# Sparki_Rev15.net
KiCad netlist of a schematic drawn in EAGLE
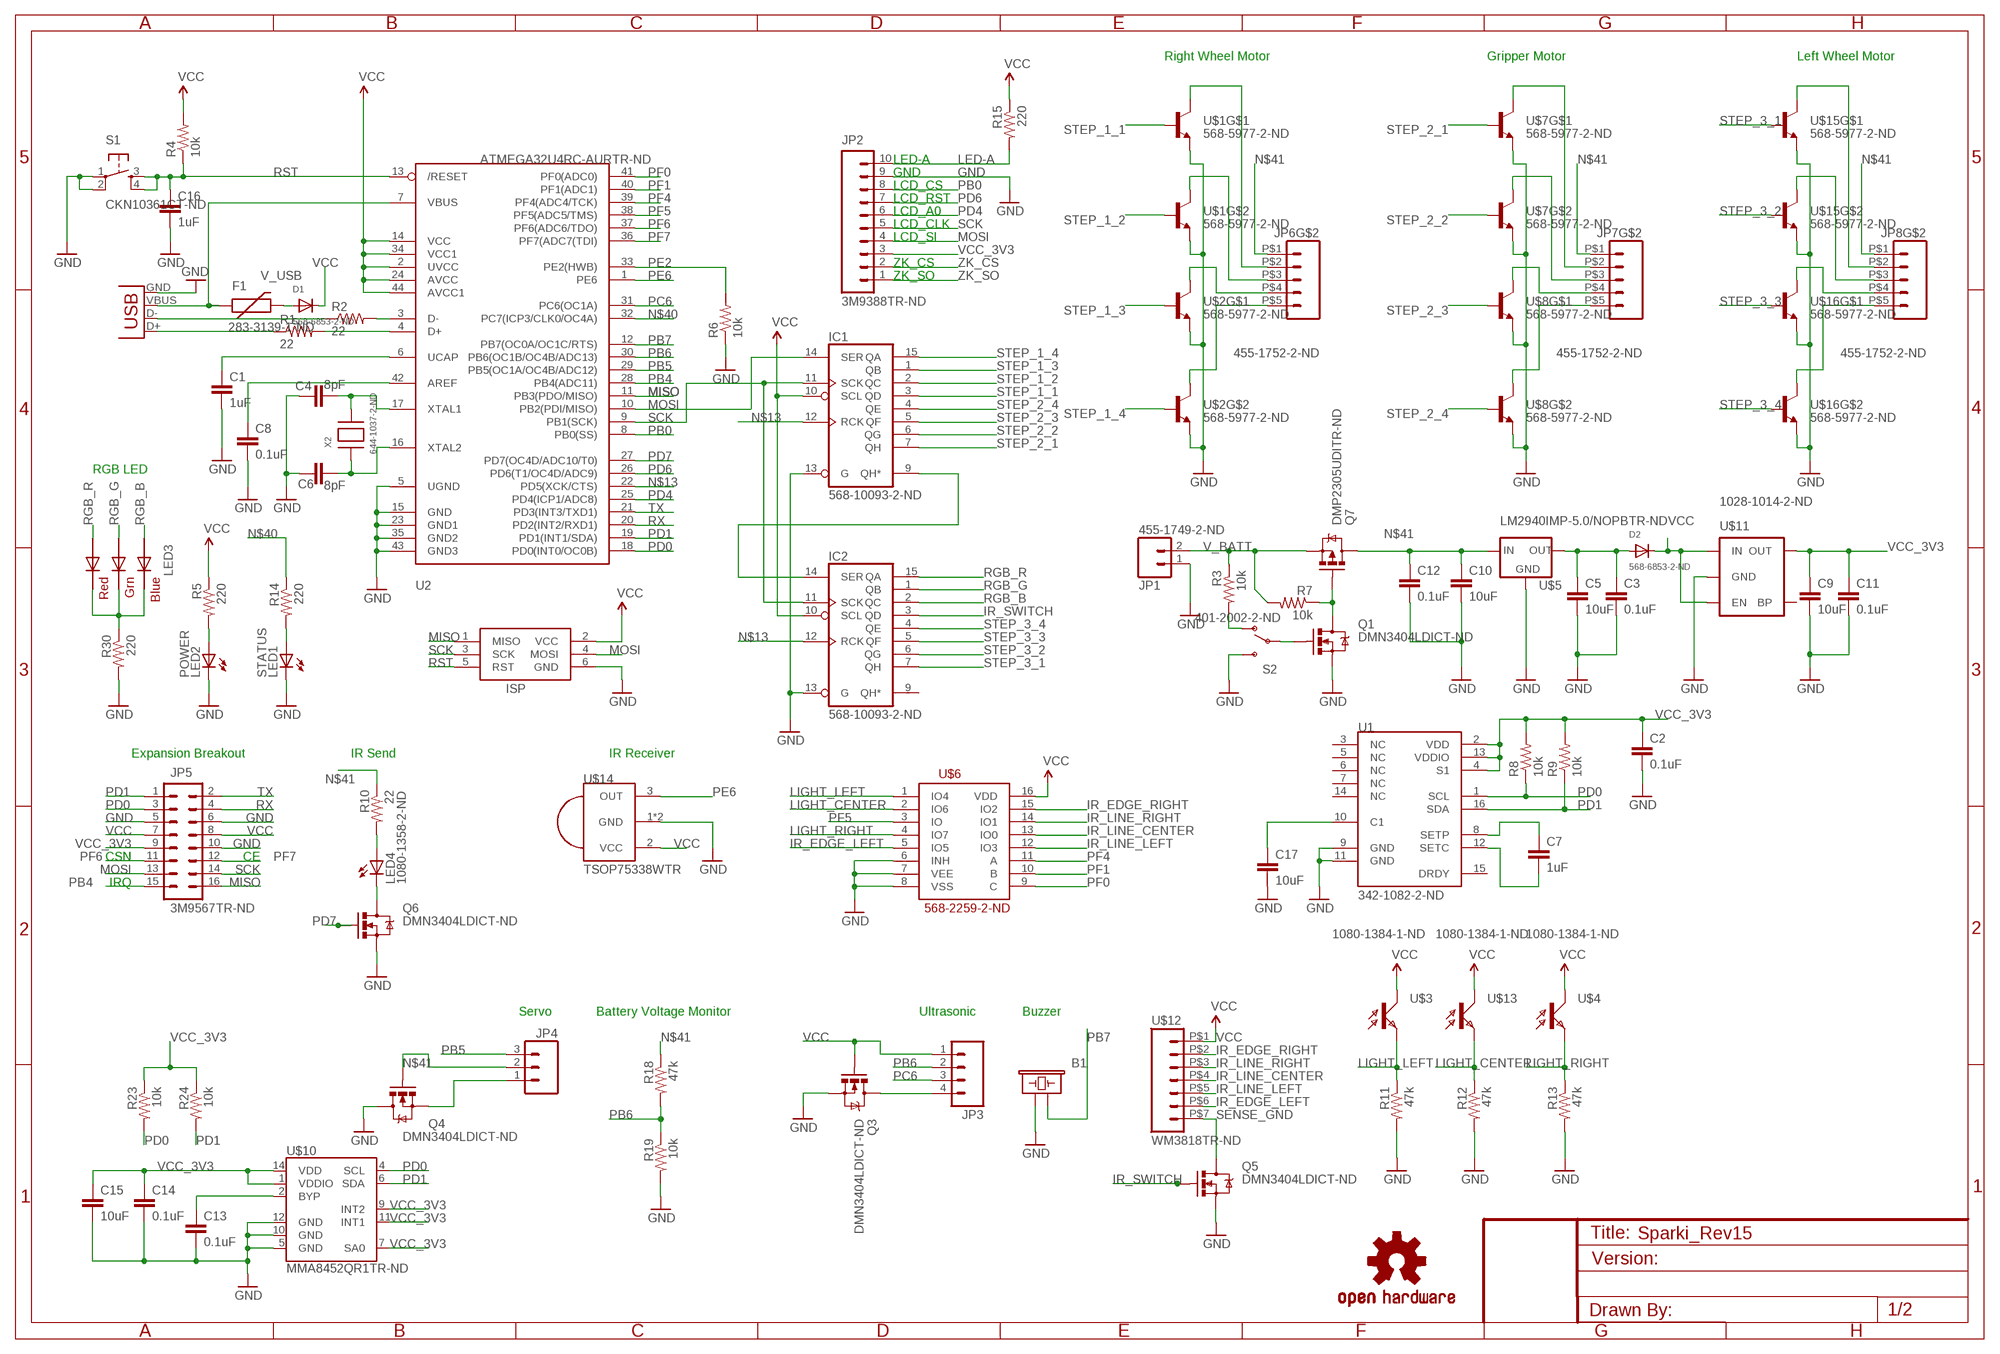
[diagram p0: schematic, sheet 1]
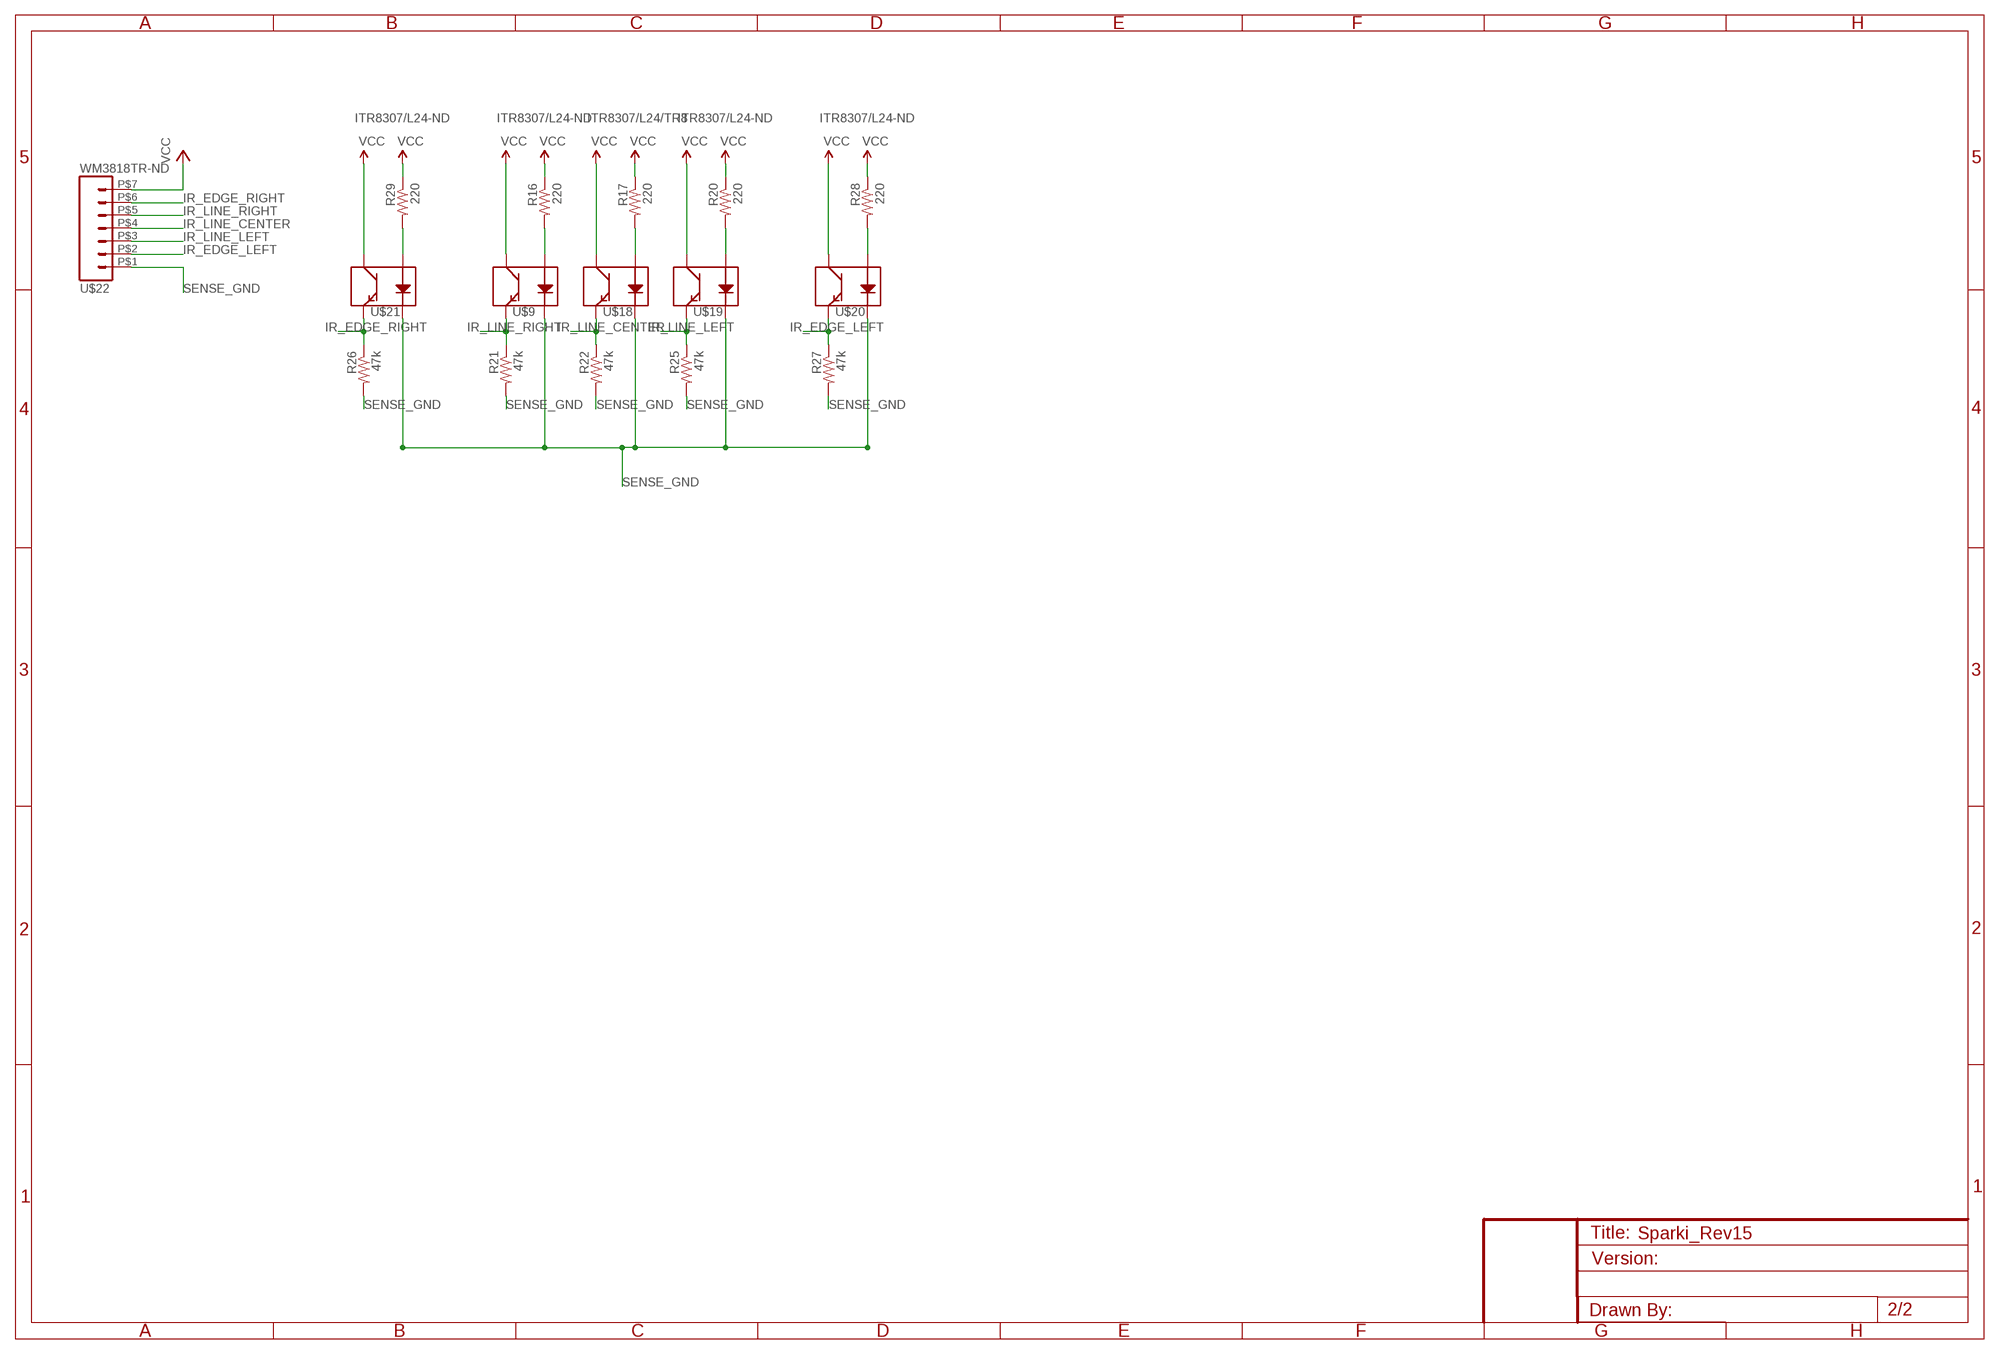
[diagram p1: schematic, sheet 2]

(export (version "E")
  (design (tool "Eeschema 10.0.6"))
  (components
    (comp (ref "B1")
      (value "SMT-0927-T-2-R")
      (footprint "eagle-import:BUZZER-CCV")
      (libsource (lib "eagle-import") (part "BUZZERSMD2"))
    )
    (comp (ref "C1")
      (value "1uF")
      (footprint "eagle-import:0603-CAP")
      (libsource (lib "eagle-import") (part "SparkFun-Passives_CAP0603-CAP"))
    )
    (comp (ref "C2")
      (value "0.1uF")
      (footprint "eagle-import:0603-CAP")
      (libsource (lib "eagle-import") (part "CAP0603-CAP"))
    )
    (comp (ref "C3")
      (value "0.1uF")
      (footprint "eagle-import:0603-CAP")
      (libsource (lib "eagle-import") (part "SparkFun-Passives_CAP0603-CAP"))
    )
    (comp (ref "C4")
      (value "8pF")
      (footprint "eagle-import:0603-CAP")
      (libsource (lib "eagle-import") (part "SparkFun-Passives_CAP0603-CAP"))
    )
    (comp (ref "C5")
      (value "10uF")
      (footprint "eagle-import:0805")
      (libsource (lib "eagle-import") (part "SparkFun-Passives_CAP0805"))
    )
    (comp (ref "C6")
      (value "8pF")
      (footprint "eagle-import:0603-CAP")
      (libsource (lib "eagle-import") (part "SparkFun-Passives_CAP0603-CAP"))
    )
    (comp (ref "C7")
      (value "1uF")
      (footprint "eagle-import:0603-CAP")
      (libsource (lib "eagle-import") (part "CAP0603-CAP"))
    )
    (comp (ref "C8")
      (value "0.1uF")
      (footprint "eagle-import:0603-CAP")
      (libsource (lib "eagle-import") (part "SparkFun-Passives_CAP0603-CAP"))
    )
    (comp (ref "C9")
      (value "10uF")
      (footprint "eagle-import:0805")
      (libsource (lib "eagle-import") (part "SparkFun-Passives_CAP0805"))
    )
    (comp (ref "C10")
      (value "10uF")
      (footprint "eagle-import:0805")
      (libsource (lib "eagle-import") (part "SparkFun-Passives_CAP0805"))
    )
    (comp (ref "C11")
      (value "0.1uF")
      (footprint "eagle-import:0603-CAP")
      (libsource (lib "eagle-import") (part "SparkFun-Passives_CAP0603-CAP"))
    )
    (comp (ref "C12")
      (value "0.1uF")
      (footprint "eagle-import:0603-CAP")
      (libsource (lib "eagle-import") (part "SparkFun-Passives_CAP0603-CAP"))
    )
    (comp (ref "C13")
      (value "0.1uF")
      (footprint "eagle-import:0603-CAP")
      (libsource (lib "eagle-import") (part "SparkFun-Passives_CAP0603-CAP"))
    )
    (comp (ref "C14")
      (value "0.1uF")
      (footprint "eagle-import:0603-CAP")
      (libsource (lib "eagle-import") (part "SparkFun-Passives_CAP0603-CAP"))
    )
    (comp (ref "C15")
      (value "10uF")
      (footprint "eagle-import:0805")
      (libsource (lib "eagle-import") (part "SparkFun-Passives_CAP0805"))
    )
    (comp (ref "C16")
      (value "1uF")
      (footprint "eagle-import:0603-CAP")
      (libsource (lib "eagle-import") (part "SparkFun-Passives_CAP0603-CAP"))
    )
    (comp (ref "C17")
      (value "10uF")
      (footprint "eagle-import:0805")
      (libsource (lib "eagle-import") (part "SparkFun-Passives_CAP0805"))
    )
    (comp (ref "D1")
      (value "568-6853-2-ND")
      (footprint "eagle-import:SOD-128")
      (libsource (lib "eagle-import") (part "PMEG3010EP"))
    )
    (comp (ref "D2")
      (value "568-6853-2-ND")
      (footprint "eagle-import:SOD-128")
      (libsource (lib "eagle-import") (part "PMEG3010EP"))
    )
    (comp (ref "F1")
      (value "283-3139-1-ND")
      (footprint "eagle-import:PTC-1206")
      (libsource (lib "eagle-import") (part "PTCSMD"))
    )
    (comp (ref "IC1")
      (value "568-10093-2-ND")
      (footprint "eagle-import:TSSOP16")
      (libsource (lib "eagle-import") (part "74595"))
    )
    (comp (ref "IC2")
      (value "568-10093-2-ND")
      (footprint "eagle-import:TSSOP16")
      (libsource (lib "eagle-import") (part "74595"))
    )
    (comp (ref "ISP")
      (value "AVRISP-6")
      (footprint "eagle-import:AVRISP")
      (libsource (lib "eagle-import") (part "AVRISP-6"))
    )
    (comp (ref "JP1")
      (value "455-1749-2-ND")
      (footprint "eagle-import:JST-2-SMD")
      (libsource (lib "eagle-import") (part "M02-JST-2MM-SMT"))
    )
    (comp (ref "JP2")
      (value "3M9388TR-ND")
      (footprint "eagle-import:1X10-2.54MM-SMD")
      (libsource (lib "eagle-import") (part "M10"))
    )
    (comp (ref "JP3")
      (value "3M12031-ND")
      (footprint "eagle-import:1X04-2.54MM-SMD")
      (libsource (lib "eagle-import") (part "M04SMD3"))
    )
    (comp (ref "JP4")
      (value "M20-8900305-ND")
      (footprint "eagle-import:1X03_SMD_RA_MALE")
      (libsource (lib "eagle-import") (part "M03SMD_RA_MALE"))
    )
    (comp (ref "JP5")
      (value "3M9567TR-ND")
      (footprint "eagle-import:2X08-2.54MM-SMD")
      (libsource (lib "eagle-import") (part "M08X2SMD"))
    )
    (comp (ref "JP6")
      (value "455-1752-2-ND")
      (footprint "eagle-import:1X05-2.0MM-JST-PH")
      (libsource (lib "eagle-import") (part "JST-PH2.0-5P"))
    )
    (comp (ref "JP7")
      (value "455-1752-2-ND")
      (footprint "eagle-import:1X05-2.0MM-JST-PH")
      (libsource (lib "eagle-import") (part "JST-PH2.0-5P"))
    )
    (comp (ref "JP8")
      (value "455-1752-2-ND")
      (footprint "eagle-import:1X05-2.0MM-JST-PH")
      (libsource (lib "eagle-import") (part "JST-PH2.0-5P"))
    )
    (comp (ref "LED1")
      (value "STATUS")
      (footprint "eagle-import:SML0805")
      (libsource (lib "eagle-import") (part "LEDSML0805"))
    )
    (comp (ref "LED2")
      (value "POWER")
      (footprint "eagle-import:SML0805")
      (libsource (lib "eagle-import") (part "LEDSML0805"))
    )
    (comp (ref "LED3")
      (value "PLCC6RGBCT")
      (footprint "eagle-import:RGBLED5050")
      (libsource (lib "eagle-import") (part "RGBLED5050"))
    )
    (comp (ref "LED4")
      (value "1080-1358-2-ND")
      (footprint "eagle-import:FKIT-LED-1206")
      (libsource (lib "eagle-import") (part "LED-FKIT-1206"))
    )
    (comp (ref "LOGO1")
      (value "OSHW-LOGOM")
      (footprint "eagle-import:OSHW-LOGO-M")
      (libsource (lib "eagle-import") (part "OSHW-LOGOM"))
    )
    (comp (ref "Q1")
      (value "DMN3404LDICT-ND")
      (footprint "eagle-import:SOT23-3")
      (libsource (lib "eagle-import") (part "MOSFET-NCHANNELSMD"))
    )
    (comp (ref "Q3")
      (value "DMN3404LDICT-ND")
      (footprint "eagle-import:SOT23-3")
      (libsource (lib "eagle-import") (part "MOSFET-NCHANNELSMD"))
    )
    (comp (ref "Q4")
      (value "DMN3404LDICT-ND")
      (footprint "eagle-import:SOT23-3")
      (libsource (lib "eagle-import") (part "MOSFET-NCHANNELSMD"))
    )
    (comp (ref "Q5")
      (value "DMN3404LDICT-ND")
      (footprint "eagle-import:SOT23-3")
      (libsource (lib "eagle-import") (part "MOSFET-NCHANNELSMD"))
    )
    (comp (ref "Q6")
      (value "DMN3404LDICT-ND")
      (footprint "eagle-import:SOT23-3")
      (libsource (lib "eagle-import") (part "MOSFET-NCHANNELSMD"))
    )
    (comp (ref "Q7")
      (value "DMP2305UDITR-ND")
      (footprint "eagle-import:SOT23-3")
      (libsource (lib "eagle-import") (part "MOSFET-PCHANNELSMD"))
    )
    (comp (ref "R1")
      (value "22")
      (footprint "eagle-import:0603-RES")
      (libsource (lib "eagle-import") (part "RESISTOR0603-RES"))
    )
    (comp (ref "R2")
      (value "22")
      (footprint "eagle-import:0603-RES")
      (libsource (lib "eagle-import") (part "RESISTOR0603-RES"))
    )
    (comp (ref "R3")
      (value "10k")
      (footprint "eagle-import:0603-RES")
      (libsource (lib "eagle-import") (part "RESISTOR0603-RES"))
    )
    (comp (ref "R4")
      (value "10k")
      (footprint "eagle-import:0603-RES")
      (libsource (lib "eagle-import") (part "RESISTOR0603-RES"))
    )
    (comp (ref "R5")
      (value "220")
      (footprint "eagle-import:0603-RES")
      (libsource (lib "eagle-import") (part "RESISTOR0603-RES"))
    )
    (comp (ref "R6")
      (value "10k")
      (footprint "eagle-import:0603-RES")
      (libsource (lib "eagle-import") (part "RESISTOR0603-RES"))
    )
    (comp (ref "R7")
      (value "10k")
      (footprint "eagle-import:0603-RES")
      (libsource (lib "eagle-import") (part "RESISTOR0603-RES"))
    )
    (comp (ref "R8")
      (value "10k")
      (footprint "eagle-import:0603-RES")
      (libsource (lib "eagle-import") (part "SparkFun-Resistors_RESISTOR0603-RES"))
    )
    (comp (ref "R9")
      (value "10k")
      (footprint "eagle-import:0603-RES")
      (libsource (lib "eagle-import") (part "SparkFun-Resistors_RESISTOR0603-RES"))
    )
    (comp (ref "R10")
      (value "22")
      (footprint "eagle-import:0603-RES")
      (libsource (lib "eagle-import") (part "RESISTOR0603-RES"))
    )
    (comp (ref "R11")
      (value "47k")
      (footprint "eagle-import:0603-RES")
      (libsource (lib "eagle-import") (part "RESISTOR0603-RES"))
    )
    (comp (ref "R12")
      (value "47k")
      (footprint "eagle-import:0603-RES")
      (libsource (lib "eagle-import") (part "RESISTOR0603-RES"))
    )
    (comp (ref "R13")
      (value "47k")
      (footprint "eagle-import:0603-RES")
      (libsource (lib "eagle-import") (part "RESISTOR0603-RES"))
    )
    (comp (ref "R14")
      (value "220")
      (footprint "eagle-import:0603-RES")
      (libsource (lib "eagle-import") (part "RESISTOR0603-RES"))
    )
    (comp (ref "R15")
      (value "220")
      (footprint "eagle-import:0603-RES")
      (libsource (lib "eagle-import") (part "RESISTOR0603-RES"))
    )
    (comp (ref "R18")
      (value "47k")
      (footprint "eagle-import:0603-RES")
      (libsource (lib "eagle-import") (part "RESISTOR0603-RES"))
    )
    (comp (ref "R19")
      (value "10k")
      (footprint "eagle-import:0603-RES")
      (libsource (lib "eagle-import") (part "RESISTOR0603-RES"))
    )
    (comp (ref "R23")
      (value "10k")
      (footprint "eagle-import:0603-RES")
      (libsource (lib "eagle-import") (part "RESISTOR0603-RES"))
    )
    (comp (ref "R24")
      (value "10k")
      (footprint "eagle-import:0603-RES")
      (libsource (lib "eagle-import") (part "RESISTOR0603-RES"))
    )
    (comp (ref "R30")
      (value "220")
      (footprint "eagle-import:0603-RES")
      (libsource (lib "eagle-import") (part "RESISTOR0603-RES"))
    )
    (comp (ref "S1")
      (value "CKN10361CT-ND")
      (footprint "eagle-import:TACTILE_SWITCH_SMD")
      (libsource (lib "eagle-import") (part "TAC_SWITCHSMD"))
    )
    (comp (ref "S2")
      (value "401-2002-2-ND")
      (footprint "eagle-import:AYZ0202")
      (libsource (lib "eagle-import") (part "SWITCH-SPDTSMD"))
    )
    (comp (ref "U$1")
      (value "568-5977-2-ND")
      (footprint "eagle-import:SOT363")
      (libsource (lib "eagle-import") (part "MMDT3904"))
    )
    (comp (ref "U$2")
      (value "568-5977-2-ND")
      (footprint "eagle-import:SOT363")
      (libsource (lib "eagle-import") (part "MMDT3904"))
    )
    (comp (ref "U$3")
      (value "1080-1384-1-ND")
      (footprint "eagle-import:LED-0402")
      (libsource (lib "eagle-import") (part "PHOTOTRANSISTOR0402"))
    )
    (comp (ref "U$4")
      (value "1080-1384-1-ND")
      (footprint "eagle-import:LED-0402")
      (libsource (lib "eagle-import") (part "PHOTOTRANSISTOR0402"))
    )
    (comp (ref "U$5")
      (value "LM2940IMP-5.0/NOPBTR-ND")
      (footprint "eagle-import:SOT223")
      (libsource (lib "eagle-import") (part "V_REG_MIC2920"))
    )
    (comp (ref "U$6")
      (value "568-2259-2-ND")
      (footprint "eagle-import:TSSOP-16")
      (libsource (lib "eagle-import") (part "74HC4051_MUXTSSOP-16"))
    )
    (comp (ref "U$7")
      (value "568-5977-2-ND")
      (footprint "eagle-import:SOT363")
      (libsource (lib "eagle-import") (part "MMDT3904"))
    )
    (comp (ref "U$8")
      (value "568-5977-2-ND")
      (footprint "eagle-import:SOT363")
      (libsource (lib "eagle-import") (part "MMDT3904"))
    )
    (comp (ref "U$10")
      (value "MMA8452QR1TR-ND")
      (footprint "eagle-import:QFN-16_0.5MM")
      (libsource (lib "eagle-import") (part "MMA8452Q"))
    )
    (comp (ref "U$11")
      (value "1028-1014-2-ND")
      (footprint "eagle-import:SOT23-5")
      (libsource (lib "eagle-import") (part "V_REG_LDOSMD"))
    )
    (comp (ref "U$12")
      (value "WM3818TR-ND")
      (footprint "eagle-import:1X07-1.0MM-FPC")
      (libsource (lib "eagle-import") (part "FPC-1.0MM-7P"))
    )
    (comp (ref "U$13")
      (value "1080-1384-1-ND")
      (footprint "eagle-import:LED-0402")
      (libsource (lib "eagle-import") (part "PHOTOTRANSISTOR0402"))
    )
    (comp (ref "U$14")
      (value "TSOP75338WTR")
      (footprint "eagle-import:TSOP75338")
      (libsource (lib "eagle-import") (part "TSOP75338"))
    )
    (comp (ref "U$15")
      (value "568-5977-2-ND")
      (footprint "eagle-import:SOT363")
      (libsource (lib "eagle-import") (part "MMDT3904"))
    )
    (comp (ref "U$16")
      (value "568-5977-2-ND")
      (footprint "eagle-import:SOT363")
      (libsource (lib "eagle-import") (part "MMDT3904"))
    )
    (comp (ref "U1")
      (value "342-1082-2-ND")
      (footprint "eagle-import:16LPCC")
      (libsource (lib "eagle-import") (part "HMC5883LSMD"))
    )
    (comp (ref "U2")
      (value "ATMEGA32U4RC-AURTR-ND")
      (footprint "eagle-import:TQFP44")
      (libsource (lib "eagle-import") (part "ATMEGA32U4-AU"))
    )
    (comp (ref "X1")
      (value "ED90342TR-ND")
      (footprint "eagle-import:USB-MINIB")
      (libsource (lib "eagle-import") (part "USBSMD"))
    )
    (comp (ref "X2")
      (value "644-1037-2-ND")
      (footprint "eagle-import:NX5032")
      (libsource (lib "eagle-import") (part "XTALNX5032"))
    )
    (comp (ref "R16")
      (value "220")
      (footprint "eagle-import:0603-RES")
      (libsource (lib "eagle-import") (part "RESISTOR0603-RES"))
    )
    (comp (ref "R17")
      (value "220")
      (footprint "eagle-import:0603-RES")
      (libsource (lib "eagle-import") (part "RESISTOR0603-RES"))
    )
    (comp (ref "R20")
      (value "220")
      (footprint "eagle-import:0603-RES")
      (libsource (lib "eagle-import") (part "RESISTOR0603-RES"))
    )
    (comp (ref "R21")
      (value "47k")
      (footprint "eagle-import:0603-RES")
      (libsource (lib "eagle-import") (part "RESISTOR0603-RES"))
    )
    (comp (ref "R22")
      (value "47k")
      (footprint "eagle-import:0603-RES")
      (libsource (lib "eagle-import") (part "RESISTOR0603-RES"))
    )
    (comp (ref "R25")
      (value "47k")
      (footprint "eagle-import:0603-RES")
      (libsource (lib "eagle-import") (part "RESISTOR0603-RES"))
    )
    (comp (ref "R26")
      (value "47k")
      (footprint "eagle-import:0603-RES")
      (libsource (lib "eagle-import") (part "RESISTOR0603-RES"))
    )
    (comp (ref "R27")
      (value "47k")
      (footprint "eagle-import:0603-RES")
      (libsource (lib "eagle-import") (part "RESISTOR0603-RES"))
    )
    (comp (ref "R28")
      (value "220")
      (footprint "eagle-import:0603-RES")
      (libsource (lib "eagle-import") (part "RESISTOR0603-RES"))
    )
    (comp (ref "R29")
      (value "220")
      (footprint "eagle-import:0603-RES")
      (libsource (lib "eagle-import") (part "RESISTOR0603-RES"))
    )
    (comp (ref "U$9")
      (value "ITR8307/L24-ND")
      (footprint "eagle-import:QRE1113")
      (libsource (lib "eagle-import") (part "QRE1113"))
    )
    (comp (ref "U$18")
      (value "ITR8307/L24/TR8")
      (footprint "eagle-import:QRE1113")
      (libsource (lib "eagle-import") (part "QRE1113"))
    )
    (comp (ref "U$19")
      (value "ITR8307/L24-ND")
      (footprint "eagle-import:QRE1113")
      (libsource (lib "eagle-import") (part "QRE1113"))
    )
    (comp (ref "U$20")
      (value "ITR8307/L24-ND")
      (footprint "eagle-import:QRE1113")
      (libsource (lib "eagle-import") (part "QRE1113"))
    )
    (comp (ref "U$21")
      (value "ITR8307/L24-ND")
      (footprint "eagle-import:QRE1113")
      (libsource (lib "eagle-import") (part "QRE1113"))
    )
    (comp (ref "U$22")
      (value "WM3818TR-ND")
      (footprint "eagle-import:1X07-1.0MM-FPC")
      (libsource (lib "eagle-import") (part "FPC-1.0MM-7P"))
    )
  )
  (nets
    (net (code "1") (name "GND") (class "Default")
      (node (ref "B1") (pin "-") (pinfunction "2_-") (pintype "passive"))
      (node (ref "C1") (pin "2") (pinfunction "2_2") (pintype "passive"))
      (node (ref "C10") (pin "2") (pinfunction "2_2") (pintype "passive"))
      (node (ref "C11") (pin "2") (pinfunction "2_2") (pintype "passive"))
      (node (ref "C12") (pin "2") (pinfunction "2_2") (pintype "passive"))
      (node (ref "C13") (pin "2") (pinfunction "2_2") (pintype "passive"))
      (node (ref "C14") (pin "2") (pinfunction "2_2") (pintype "passive"))
      (node (ref "C15") (pin "2") (pinfunction "2_2") (pintype "passive"))
      (node (ref "C16") (pin "2") (pinfunction "2_2") (pintype "passive"))
      (node (ref "C17") (pin "2") (pinfunction "2_2") (pintype "passive"))
      (node (ref "C2") (pin "2") (pinfunction "2_2") (pintype "passive"))
      (node (ref "C3") (pin "2") (pinfunction "2_2") (pintype "passive"))
      (node (ref "C4") (pin "2") (pinfunction "2_2") (pintype "passive"))
      (node (ref "C5") (pin "2") (pinfunction "2_2") (pintype "passive"))
      (node (ref "C6") (pin "2") (pinfunction "2_2") (pintype "passive"))
      (node (ref "C8") (pin "2") (pinfunction "2_2") (pintype "passive"))
      (node (ref "C9") (pin "2") (pinfunction "2_2") (pintype "passive"))
      (node (ref "IC1") (pin "13") (pinfunction "G_13") (pintype "input"))
      (node (ref "IC2") (pin "13") (pinfunction "G_13") (pintype "input"))
      (node (ref "ISP") (pin "6") (pinfunction "GND_6") (pintype "power_in"))
      (node (ref "JP1") (pin "1") (pinfunction "2_1") (pintype "passive"))
      (node (ref "JP2") (pin "9") (pinfunction "9_9") (pintype "passive"))
      (node (ref "JP5") (pin "10") (pinfunction "10_10") (pintype "passive"))
      (node (ref "JP5") (pin "5") (pinfunction "5_5") (pintype "passive"))
      (node (ref "JP5") (pin "6") (pinfunction "6_6") (pintype "passive"))
      (node (ref "LED1") (pin "C") (pinfunction "C_C") (pintype "passive"))
      (node (ref "LED2") (pin "C") (pinfunction "C_C") (pintype "passive"))
      (node (ref "Q1") (pin "2") (pinfunction "S_2") (pintype "passive"))
      (node (ref "Q3") (pin "2") (pinfunction "S_2") (pintype "passive"))
      (node (ref "Q4") (pin "3") (pinfunction "D_3") (pintype "passive"))
      (node (ref "Q5") (pin "2") (pinfunction "S_2") (pintype "passive"))
      (node (ref "Q6") (pin "2") (pinfunction "S_2") (pintype "passive"))
      (node (ref "R11") (pin "2") (pinfunction "2_2") (pintype "passive"))
      (node (ref "R12") (pin "2") (pinfunction "2_2") (pintype "passive"))
      (node (ref "R13") (pin "2") (pinfunction "2_2") (pintype "passive"))
      (node (ref "R19") (pin "2") (pinfunction "2_2") (pintype "passive"))
      (node (ref "R30") (pin "2") (pinfunction "2_2") (pintype "passive"))
      (node (ref "R6") (pin "1") (pinfunction "1_1") (pintype "passive"))
      (node (ref "S1") (pin "1") (pinfunction "1_1") (pintype "passive"))
      (node (ref "S1") (pin "2") (pinfunction "2_2") (pintype "passive"))
      (node (ref "S2") (pin "3") (pinfunction "S_3") (pintype "passive"))
      (node (ref "U$1") (pin "1") (pinfunction "E_1") (pintype "passive"))
      (node (ref "U$1") (pin "4") (pinfunction "E_4") (pintype "passive"))
      (node (ref "U$10") (pin "10") (pinfunction "GND_10") (pintype "bidirectional"))
      (node (ref "U$10") (pin "12") (pinfunction "GND_12") (pintype "bidirectional"))
      (node (ref "U$10") (pin "5") (pinfunction "GND_5") (pintype "bidirectional"))
      (node (ref "U$11") (pin "2") (pinfunction "GND_2") (pintype "input"))
      (node (ref "U$14") (pin "1") (pinfunction "GND_1") (pintype "power_in"))
      (node (ref "U$14") (pin "4") (pinfunction "GND_4") (pintype "power_in"))
      (node (ref "U$15") (pin "1") (pinfunction "E_1") (pintype "passive"))
      (node (ref "U$15") (pin "4") (pinfunction "E_4") (pintype "passive"))
      (node (ref "U$16") (pin "1") (pinfunction "E_1") (pintype "passive"))
      (node (ref "U$16") (pin "4") (pinfunction "E_4") (pintype "passive"))
      (node (ref "U$2") (pin "1") (pinfunction "E_1") (pintype "passive"))
      (node (ref "U$2") (pin "4") (pinfunction "E_4") (pintype "passive"))
      (node (ref "U$5") (pin "2") (pinfunction "GND_2") (pintype "input"))
      (node (ref "U$6") (pin "6") (pinfunction "INH_6") (pintype "bidirectional"))
      (node (ref "U$6") (pin "7") (pinfunction "VEE_7") (pintype "bidirectional"))
      (node (ref "U$6") (pin "8") (pinfunction "VSS_8") (pintype "bidirectional"))
      (node (ref "U$7") (pin "1") (pinfunction "E_1") (pintype "passive"))
      (node (ref "U$7") (pin "4") (pinfunction "E_4") (pintype "passive"))
      (node (ref "U$8") (pin "1") (pinfunction "E_1") (pintype "passive"))
      (node (ref "U$8") (pin "4") (pinfunction "E_4") (pintype "passive"))
      (node (ref "U1") (pin "11") (pinfunction "GND_11") (pintype "bidirectional"))
      (node (ref "U1") (pin "9") (pinfunction "GND_9") (pintype "bidirectional"))
      (node (ref "U2") (pin "15") (pinfunction "GND_15") (pintype "bidirectional"))
      (node (ref "U2") (pin "23") (pinfunction "GND1_23") (pintype "bidirectional"))
      (node (ref "U2") (pin "35") (pinfunction "GND2_35") (pintype "bidirectional"))
      (node (ref "U2") (pin "43") (pinfunction "GND3_43") (pintype "bidirectional"))
      (node (ref "U2") (pin "5") (pinfunction "UGND_5") (pintype "bidirectional"))
      (node (ref "X1") (pin "GND") (pinfunction "GND_GND") (pintype "bidirectional"))
    )
    (net (code "2") (name "IR_EDGE_LEFT") (class "Default")
      (node (ref "R27") (pin "1") (pinfunction "1_1") (pintype "passive"))
      (node (ref "U$12") (pin "P$6") (pinfunction "6_P$6") (pintype "passive"))
      (node (ref "U$20") (pin "4") (pinfunction "E_4") (pintype "bidirectional"))
      (node (ref "U$22") (pin "P$2") (pinfunction "2_P$2") (pintype "passive"))
      (node (ref "U$6") (pin "5") (pinfunction "IO5_5") (pintype "bidirectional"))
    )
    (net (code "3") (name "IR_EDGE_RIGHT") (class "Default")
      (node (ref "R26") (pin "1") (pinfunction "1_1") (pintype "passive"))
      (node (ref "U$12") (pin "P$2") (pinfunction "2_P$2") (pintype "passive"))
      (node (ref "U$21") (pin "4") (pinfunction "E_4") (pintype "bidirectional"))
      (node (ref "U$22") (pin "P$6") (pinfunction "6_P$6") (pintype "passive"))
      (node (ref "U$6") (pin "15") (pinfunction "IO2_15") (pintype "bidirectional"))
    )
    (net (code "4") (name "IR_LINE_CENTER") (class "Default")
      (node (ref "R22") (pin "1") (pinfunction "1_1") (pintype "passive"))
      (node (ref "U$12") (pin "P$4") (pinfunction "4_P$4") (pintype "passive"))
      (node (ref "U$18") (pin "4") (pinfunction "E_4") (pintype "bidirectional"))
      (node (ref "U$22") (pin "P$4") (pinfunction "4_P$4") (pintype "passive"))
      (node (ref "U$6") (pin "13") (pinfunction "IO0_13") (pintype "bidirectional"))
    )
    (net (code "5") (name "IR_LINE_LEFT") (class "Default")
      (node (ref "R25") (pin "1") (pinfunction "1_1") (pintype "passive"))
      (node (ref "U$12") (pin "P$5") (pinfunction "5_P$5") (pintype "passive"))
      (node (ref "U$19") (pin "4") (pinfunction "E_4") (pintype "bidirectional"))
      (node (ref "U$22") (pin "P$3") (pinfunction "3_P$3") (pintype "passive"))
      (node (ref "U$6") (pin "12") (pinfunction "IO3_12") (pintype "bidirectional"))
    )
    (net (code "6") (name "IR_LINE_RIGHT") (class "Default")
      (node (ref "R21") (pin "1") (pinfunction "1_1") (pintype "passive"))
      (node (ref "U$12") (pin "P$3") (pinfunction "3_P$3") (pintype "passive"))
      (node (ref "U$22") (pin "P$5") (pinfunction "5_P$5") (pintype "passive"))
      (node (ref "U$6") (pin "14") (pinfunction "IO1_14") (pintype "bidirectional"))
      (node (ref "U$9") (pin "4") (pinfunction "E_4") (pintype "bidirectional"))
    )
    (net (code "7") (name "IR_SWITCH") (class "Default")
      (node (ref "IC2") (pin "3") (pinfunction "QD_3") (pintype "tri_state"))
      (node (ref "Q5") (pin "1") (pinfunction "G_1") (pintype "passive"))
    )
    (net (code "8") (name "LED-A") (class "Default")
      (node (ref "JP2") (pin "10") (pinfunction "10_10") (pintype "passive"))
      (node (ref "R15") (pin "2") (pinfunction "2_2") (pintype "passive"))
    )
    (net (code "9") (name "LIGHT_CENTER") (class "Default")
      (node (ref "R12") (pin "1") (pinfunction "1_1") (pintype "passive"))
      (node (ref "U$13") (pin "2") (pinfunction "E_2") (pintype "passive"))
      (node (ref "U$6") (pin "2") (pinfunction "IO6_2") (pintype "bidirectional"))
    )
    (net (code "10") (name "LIGHT_LEFT") (class "Default")
      (node (ref "R11") (pin "1") (pinfunction "1_1") (pintype "passive"))
      (node (ref "U$3") (pin "2") (pinfunction "E_2") (pintype "passive"))
      (node (ref "U$6") (pin "1") (pinfunction "IO4_1") (pintype "bidirectional"))
    )
    (net (code "11") (name "LIGHT_RIGHT") (class "Default")
      (node (ref "R13") (pin "1") (pinfunction "1_1") (pintype "passive"))
      (node (ref "U$4") (pin "2") (pinfunction "E_2") (pintype "passive"))
      (node (ref "U$6") (pin "4") (pinfunction "IO7_4") (pintype "bidirectional"))
    )
    (net (code "12") (name "MISO") (class "Default")
      (node (ref "ISP") (pin "1") (pinfunction "MISO_1") (pintype "input"))
      (node (ref "JP5") (pin "16") (pinfunction "16_16") (pintype "passive"))
      (node (ref "U2") (pin "11") (pinfunction "PB3(PDO/MISO)_11") (pintype "bidirectional"))
    )
    (net (code "13") (name "MOSI") (class "Default")
      (node (ref "IC1") (pin "14") (pinfunction "SER_14") (pintype "input"))
      (node (ref "ISP") (pin "4") (pinfunction "MOSI_4") (pintype "output"))
      (node (ref "JP2") (pin "4") (pinfunction "4_4") (pintype "passive"))
      (node (ref "JP5") (pin "13") (pinfunction "13_13") (pintype "passive"))
      (node (ref "U2") (pin "10") (pinfunction "PB2(PDI/MISO)_10") (pintype "bidirectional"))
    )
    (net (code "14") (name "N$13") (class "Default")
      (node (ref "IC1") (pin "12") (pinfunction "RCK_12") (pintype "input"))
      (node (ref "IC2") (pin "12") (pinfunction "RCK_12") (pintype "input"))
      (node (ref "U2") (pin "22") (pinfunction "PD5(XCK/CTS)_22") (pintype "bidirectional"))
    )
    (net (code "15") (name "N$40") (class "Default")
      (node (ref "R14") (pin "1") (pinfunction "1_1") (pintype "passive"))
      (node (ref "U2") (pin "32") (pinfunction "PC7(ICP3/CLK0/OC4A)_32") (pintype "bidirectional"))
    )
    (net (code "16") (name "N$41") (class "Default")
      (node (ref "C10") (pin "1") (pinfunction "1_1") (pintype "passive"))
      (node (ref "C12") (pin "1") (pinfunction "1_1") (pintype "passive"))
      (node (ref "JP4") (pin "2") (pinfunction "2_2") (pintype "passive"))
      (node (ref "JP6") (pin "P$1") (pinfunction "1_P$1") (pintype "passive"))
      (node (ref "JP7") (pin "P$1") (pinfunction "1_P$1") (pintype "passive"))
      (node (ref "JP8") (pin "P$1") (pinfunction "1_P$1") (pintype "passive"))
      (node (ref "Q4") (pin "1") (pinfunction "G_1") (pintype "passive"))
      (node (ref "Q7") (pin "3") (pinfunction "D_3") (pintype "passive"))
      (node (ref "R10") (pin "1") (pinfunction "1_1") (pintype "passive"))
      (node (ref "R18") (pin "1") (pinfunction "1_1") (pintype "passive"))
      (node (ref "U$5") (pin "1") (pinfunction "IN_1") (pintype "input"))
    )
    (net (code "17") (name "Net-(D2-A)") (class "Default")
      (node (ref "C3") (pin "1") (pinfunction "1_1") (pintype "passive"))
      (node (ref "C5") (pin "1") (pinfunction "1_1") (pintype "passive"))
      (node (ref "D2") (pin "P$2") (pinfunction "A_P$2") (pintype "passive"))
      (node (ref "U$5") (pin "3") (pinfunction "OUT_3") (pintype "output"))
    )
    (net (code "18") (name "Net-(IC1A-QH*)") (class "Default")
      (node (ref "IC1") (pin "9") (pinfunction "QH*_9") (pintype "tri_state"))
      (node (ref "IC2") (pin "14") (pinfunction "SER_14") (pintype "input"))
    )
    (net (code "19") (name "Net-(JP6B-2)") (class "Default")
      (node (ref "JP6") (pin "P$2") (pinfunction "2_P$2") (pintype "passive"))
      (node (ref "U$1") (pin "3") (pinfunction "C_3") (pintype "passive"))
    )
    (net (code "20") (name "Net-(JP6B-3)") (class "Default")
      (node (ref "JP6") (pin "P$3") (pinfunction "3_P$3") (pintype "passive"))
      (node (ref "U$1") (pin "6") (pinfunction "C_6") (pintype "passive"))
    )
    (net (code "21") (name "Net-(JP6B-4)") (class "Default")
      (node (ref "JP6") (pin "P$4") (pinfunction "4_P$4") (pintype "passive"))
      (node (ref "U$2") (pin "3") (pinfunction "C_3") (pintype "passive"))
    )
    (net (code "22") (name "Net-(JP6B-5)") (class "Default")
      (node (ref "JP6") (pin "P$5") (pinfunction "5_P$5") (pintype "passive"))
      (node (ref "U$2") (pin "6") (pinfunction "C_6") (pintype "passive"))
    )
    (net (code "23") (name "Net-(JP7B-2)") (class "Default")
      (node (ref "JP7") (pin "P$2") (pinfunction "2_P$2") (pintype "passive"))
      (node (ref "U$7") (pin "3") (pinfunction "C_3") (pintype "passive"))
    )
    (net (code "24") (name "Net-(JP7B-3)") (class "Default")
      (node (ref "JP7") (pin "P$3") (pinfunction "3_P$3") (pintype "passive"))
      (node (ref "U$7") (pin "6") (pinfunction "C_6") (pintype "passive"))
    )
    (net (code "25") (name "Net-(JP7B-4)") (class "Default")
      (node (ref "JP7") (pin "P$4") (pinfunction "4_P$4") (pintype "passive"))
      (node (ref "U$8") (pin "3") (pinfunction "C_3") (pintype "passive"))
    )
    (net (code "26") (name "Net-(JP7B-5)") (class "Default")
      (node (ref "JP7") (pin "P$5") (pinfunction "5_P$5") (pintype "passive"))
      (node (ref "U$8") (pin "6") (pinfunction "C_6") (pintype "passive"))
    )
    (net (code "27") (name "Net-(JP8B-2)") (class "Default")
      (node (ref "JP8") (pin "P$2") (pinfunction "2_P$2") (pintype "passive"))
      (node (ref "U$15") (pin "3") (pinfunction "C_3") (pintype "passive"))
    )
    (net (code "28") (name "Net-(JP8B-3)") (class "Default")
      (node (ref "JP8") (pin "P$3") (pinfunction "3_P$3") (pintype "passive"))
      (node (ref "U$15") (pin "6") (pinfunction "C_6") (pintype "passive"))
    )
    (net (code "29") (name "Net-(JP8B-4)") (class "Default")
      (node (ref "JP8") (pin "P$4") (pinfunction "4_P$4") (pintype "passive"))
      (node (ref "U$16") (pin "3") (pinfunction "C_3") (pintype "passive"))
    )
    (net (code "30") (name "Net-(JP8B-5)") (class "Default")
      (node (ref "JP8") (pin "P$5") (pinfunction "5_P$5") (pintype "passive"))
      (node (ref "U$16") (pin "6") (pinfunction "C_6") (pintype "passive"))
    )
    (net (code "31") (name "Net-(LED1-PadA)") (class "Default")
      (node (ref "LED1") (pin "A") (pinfunction "A_A") (pintype "passive"))
      (node (ref "R14") (pin "2") (pinfunction "2_2") (pintype "passive"))
    )
    (net (code "32") (name "Net-(LED2-PadA)") (class "Default")
      (node (ref "LED2") (pin "A") (pinfunction "A_A") (pintype "passive"))
      (node (ref "R5") (pin "2") (pinfunction "2_2") (pintype "passive"))
    )
    (net (code "33") (name "Net-(LED3-BLUE_C)") (class "Default")
      (node (ref "LED3") (pin "4") (pinfunction "BLUE_C_4") (pintype "bidirectional"))
      (node (ref "LED3") (pin "5") (pinfunction "RED_C_5") (pintype "bidirectional"))
      (node (ref "LED3") (pin "6") (pinfunction "GREEN_C_6") (pintype "bidirectional"))
      (node (ref "R30") (pin "1") (pinfunction "1_1") (pintype "passive"))
    )
    (net (code "34") (name "Net-(LED4-PadA)") (class "Default")
      (node (ref "LED4") (pin "A") (pinfunction "A_A") (pintype "passive"))
      (node (ref "R10") (pin "2") (pinfunction "2_2") (pintype "passive"))
    )
    (net (code "35") (name "Net-(Q1-D)") (class "Default")
      (node (ref "Q1") (pin "3") (pinfunction "D_3") (pintype "passive"))
      (node (ref "Q7") (pin "1") (pinfunction "G_1") (pintype "passive"))
      (node (ref "R7") (pin "1") (pinfunction "1_1") (pintype "passive"))
    )
    (net (code "36") (name "Net-(Q1-G)") (class "Default")
      (node (ref "Q1") (pin "1") (pinfunction "G_1") (pintype "passive"))
      (node (ref "S2") (pin "2") (pinfunction "P_2") (pintype "passive"))
    )
    (net (code "37") (name "Net-(Q3-D)") (class "Default")
      (node (ref "JP3") (pin "4") (pinfunction "4_4") (pintype "passive"))
      (node (ref "Q3") (pin "3") (pinfunction "D_3") (pintype "passive"))
    )
    (net (code "38") (name "Net-(Q4-S)") (class "Default")
      (node (ref "JP4") (pin "1") (pinfunction "1_1") (pintype "passive"))
      (node (ref "Q4") (pin "2") (pinfunction "S_2") (pintype "passive"))
    )
    (net (code "39") (name "Net-(Q6-D)") (class "Default")
      (node (ref "LED4") (pin "C") (pinfunction "C_C") (pintype "passive"))
      (node (ref "Q6") (pin "3") (pinfunction "D_3") (pintype "passive"))
    )
    (net (code "40") (name "Net-(R1-Pad1)") (class "Default")
      (node (ref "R1") (pin "1") (pinfunction "1_1") (pintype "passive"))
      (node (ref "X1") (pin "D+") (pinfunction "D+_D+") (pintype "bidirectional"))
    )
    (net (code "41") (name "Net-(R2-Pad1)") (class "Default")
      (node (ref "R2") (pin "1") (pinfunction "1_1") (pintype "passive"))
      (node (ref "X1") (pin "D-") (pinfunction "D-_D-") (pintype "bidirectional"))
    )
    (net (code "42") (name "Net-(S2-O)") (class "Default")
      (node (ref "R3") (pin "2") (pinfunction "2_2") (pintype "passive"))
      (node (ref "S2") (pin "1") (pinfunction "O_1") (pintype "passive"))
    )
    (net (code "43") (name "Net-(U$9-A)") (class "Default")
      (node (ref "R16") (pin "2") (pinfunction "2_2") (pintype "passive"))
      (node (ref "U$9") (pin "1") (pinfunction "A_1") (pintype "bidirectional"))
    )
    (net (code "44") (name "Net-(U$10-BYP)") (class "Default")
      (node (ref "C13") (pin "1") (pinfunction "1_1") (pintype "passive"))
      (node (ref "U$10") (pin "2") (pinfunction "BYP_2") (pintype "bidirectional"))
    )
    (net (code "45") (name "Net-(U$18-A)") (class "Default")
      (node (ref "R17") (pin "2") (pinfunction "2_2") (pintype "passive"))
      (node (ref "U$18") (pin "1") (pinfunction "A_1") (pintype "bidirectional"))
    )
    (net (code "46") (name "Net-(U$19-A)") (class "Default")
      (node (ref "R20") (pin "2") (pinfunction "2_2") (pintype "passive"))
      (node (ref "U$19") (pin "1") (pinfunction "A_1") (pintype "bidirectional"))
    )
    (net (code "47") (name "Net-(U$20-A)") (class "Default")
      (node (ref "R28") (pin "2") (pinfunction "2_2") (pintype "passive"))
      (node (ref "U$20") (pin "1") (pinfunction "A_1") (pintype "bidirectional"))
    )
    (net (code "48") (name "Net-(U$21-A)") (class "Default")
      (node (ref "R29") (pin "2") (pinfunction "2_2") (pintype "passive"))
      (node (ref "U$21") (pin "1") (pinfunction "A_1") (pintype "bidirectional"))
    )
    (net (code "49") (name "Net-(U1-C1)") (class "Default")
      (node (ref "C17") (pin "1") (pinfunction "1_1") (pintype "passive"))
      (node (ref "U1") (pin "10") (pinfunction "C1_10") (pintype "bidirectional"))
    )
    (net (code "50") (name "Net-(U1-SETC)") (class "Default")
      (node (ref "C7") (pin "2") (pinfunction "2_2") (pintype "passive"))
      (node (ref "U1") (pin "12") (pinfunction "SETC_12") (pintype "bidirectional"))
    )
    (net (code "51") (name "Net-(U1-SETP)") (class "Default")
      (node (ref "C7") (pin "1") (pinfunction "1_1") (pintype "passive"))
      (node (ref "U1") (pin "8") (pinfunction "SETP_8") (pintype "bidirectional"))
    )
    (net (code "52") (name "Net-(U2-AREF)") (class "Default")
      (node (ref "C8") (pin "1") (pinfunction "1_1") (pintype "passive"))
      (node (ref "U2") (pin "42") (pinfunction "AREF_42") (pintype "bidirectional"))
    )
    (net (code "53") (name "Net-(U2-D+)") (class "Default")
      (node (ref "R1") (pin "2") (pinfunction "2_2") (pintype "passive"))
      (node (ref "U2") (pin "4") (pinfunction "D+_4") (pintype "bidirectional"))
    )
    (net (code "54") (name "Net-(U2-D-)") (class "Default")
      (node (ref "R2") (pin "2") (pinfunction "2_2") (pintype "passive"))
      (node (ref "U2") (pin "3") (pinfunction "D-_3") (pintype "bidirectional"))
    )
    (net (code "55") (name "Net-(U2-UCAP)") (class "Default")
      (node (ref "C1") (pin "1") (pinfunction "1_1") (pintype "passive"))
      (node (ref "U2") (pin "6") (pinfunction "UCAP_6") (pintype "bidirectional"))
    )
    (net (code "56") (name "Net-(U2-VBUS)") (class "Default")
      (node (ref "F1") (pin "1") (pinfunction "1_1") (pintype "bidirectional"))
      (node (ref "U2") (pin "7") (pinfunction "VBUS_7") (pintype "bidirectional"))
      (node (ref "X1") (pin "VBUS") (pinfunction "VBUS_VBUS") (pintype "bidirectional"))
    )
    (net (code "57") (name "Net-(U2-XTAL1)") (class "Default")
      (node (ref "C4") (pin "1") (pinfunction "1_1") (pintype "passive"))
      (node (ref "U2") (pin "17") (pinfunction "XTAL1_17") (pintype "bidirectional"))
      (node (ref "X2") (pin "P$2") (pinfunction "P$2_P$2") (pintype "bidirectional"))
    )
    (net (code "58") (name "Net-(U2-XTAL2)") (class "Default")
      (node (ref "C6") (pin "1") (pinfunction "1_1") (pintype "passive"))
      (node (ref "U2") (pin "16") (pinfunction "XTAL2_16") (pintype "bidirectional"))
      (node (ref "X2") (pin "P$1") (pinfunction "P$1_P$1") (pintype "bidirectional"))
    )
    (net (code "59") (name "PB0") (class "Default")
      (node (ref "JP2") (pin "8") (pinfunction "8_8") (pintype "passive"))
      (node (ref "U2") (pin "8") (pinfunction "PB0(SS)_8") (pintype "bidirectional"))
    )
    (net (code "60") (name "PB4") (class "Default")
      (node (ref "JP5") (pin "15") (pinfunction "15_15") (pintype "passive"))
      (node (ref "U2") (pin "28") (pinfunction "PB4(ADC11)_28") (pintype "bidirectional"))
    )
    (net (code "61") (name "PB5") (class "Default")
      (node (ref "JP4") (pin "3") (pinfunction "3_3") (pintype "passive"))
      (node (ref "U2") (pin "29") (pinfunction "PB5(OC1A/OC4B/ADC12)_29") (pintype "bidirectional"))
    )
    (net (code "62") (name "PB6") (class "Default")
      (node (ref "JP3") (pin "2") (pinfunction "2_2") (pintype "passive"))
      (node (ref "R18") (pin "2") (pinfunction "2_2") (pintype "passive"))
      (node (ref "R19") (pin "1") (pinfunction "1_1") (pintype "passive"))
      (node (ref "U2") (pin "30") (pinfunction "PB6(OC1B/OC4B/ADC13)_30") (pintype "bidirectional"))
    )
    (net (code "63") (name "PB7") (class "Default")
      (node (ref "B1") (pin "+") (pinfunction "1_+") (pintype "passive"))
      (node (ref "U2") (pin "12") (pinfunction "PB7(OC0A/OC1C/RTS)_12") (pintype "bidirectional"))
    )
    (net (code "64") (name "PC6") (class "Default")
      (node (ref "JP3") (pin "3") (pinfunction "3_3") (pintype "passive"))
      (node (ref "U2") (pin "31") (pinfunction "PC6(OC1A)_31") (pintype "bidirectional"))
    )
    (net (code "65") (name "PD0") (class "Default")
      (node (ref "JP5") (pin "3") (pinfunction "3_3") (pintype "passive"))
      (node (ref "R23") (pin "2") (pinfunction "2_2") (pintype "passive"))
      (node (ref "R8") (pin "1") (pinfunction "1_1") (pintype "passive"))
      (node (ref "U$10") (pin "4") (pinfunction "SCL_4") (pintype "bidirectional"))
      (node (ref "U1") (pin "1") (pinfunction "SCL_1") (pintype "bidirectional"))
      (node (ref "U2") (pin "18") (pinfunction "PD0(INT0/OC0B)_18") (pintype "bidirectional"))
    )
    (net (code "66") (name "PD1") (class "Default")
      (node (ref "JP5") (pin "1") (pinfunction "1_1") (pintype "passive"))
      (node (ref "R24") (pin "2") (pinfunction "2_2") (pintype "passive"))
      (node (ref "R9") (pin "1") (pinfunction "1_1") (pintype "passive"))
      (node (ref "U$10") (pin "6") (pinfunction "SDA_6") (pintype "bidirectional"))
      (node (ref "U1") (pin "16") (pinfunction "SDA_16") (pintype "bidirectional"))
      (node (ref "U2") (pin "19") (pinfunction "PD1(INT1/SDA)_19") (pintype "bidirectional"))
    )
    (net (code "67") (name "PD4") (class "Default")
      (node (ref "JP2") (pin "6") (pinfunction "6_6") (pintype "passive"))
      (node (ref "U2") (pin "25") (pinfunction "PD4(ICP1/ADC8)_25") (pintype "bidirectional"))
    )
    (net (code "68") (name "PD6") (class "Default")
      (node (ref "JP2") (pin "7") (pinfunction "7_7") (pintype "passive"))
      (node (ref "U2") (pin "26") (pinfunction "PD6(T1/OC4D/ADC9)_26") (pintype "bidirectional"))
    )
    (net (code "69") (name "PD7") (class "Default")
      (node (ref "Q6") (pin "1") (pinfunction "G_1") (pintype "passive"))
      (node (ref "U2") (pin "27") (pinfunction "PD7(OC4D/ADC10/T0)_27") (pintype "bidirectional"))
    )
    (net (code "70") (name "PE2") (class "Default")
      (node (ref "R6") (pin "2") (pinfunction "2_2") (pintype "passive"))
      (node (ref "U2") (pin "33") (pinfunction "PE2(HWB)_33") (pintype "bidirectional"))
    )
    (net (code "71") (name "PE6") (class "Default")
      (node (ref "U$14") (pin "3") (pinfunction "OUT_3") (pintype "output"))
      (node (ref "U2") (pin "1") (pinfunction "PE6_1") (pintype "bidirectional"))
    )
    (net (code "72") (name "PF0") (class "Default")
      (node (ref "U$6") (pin "9") (pinfunction "C_9") (pintype "bidirectional"))
      (node (ref "U2") (pin "41") (pinfunction "PF0(ADC0)_41") (pintype "bidirectional"))
    )
    (net (code "73") (name "PF1") (class "Default")
      (node (ref "U$6") (pin "10") (pinfunction "B_10") (pintype "bidirectional"))
      (node (ref "U2") (pin "40") (pinfunction "PF1(ADC1)_40") (pintype "bidirectional"))
    )
    (net (code "74") (name "PF4") (class "Default")
      (node (ref "U$6") (pin "11") (pinfunction "A_11") (pintype "bidirectional"))
      (node (ref "U2") (pin "39") (pinfunction "PF4(ADC4/TCK)_39") (pintype "bidirectional"))
    )
    (net (code "75") (name "PF5") (class "Default")
      (node (ref "U$6") (pin "3") (pinfunction "IO_3") (pintype "bidirectional"))
      (node (ref "U2") (pin "38") (pinfunction "PF5(ADC5/TMS)_38") (pintype "bidirectional"))
    )
    (net (code "76") (name "PF6") (class "Default")
      (node (ref "JP5") (pin "11") (pinfunction "11_11") (pintype "passive"))
      (node (ref "U2") (pin "37") (pinfunction "PF6(ADC6/TDO)_37") (pintype "bidirectional"))
    )
    (net (code "77") (name "PF7") (class "Default")
      (node (ref "JP5") (pin "12") (pinfunction "12_12") (pintype "passive"))
      (node (ref "U2") (pin "36") (pinfunction "PF7(ADC7(TDI)_36") (pintype "bidirectional"))
    )
    (net (code "78") (name "RGB_B") (class "Default")
      (node (ref "IC2") (pin "2") (pinfunction "QC_2") (pintype "tri_state"))
      (node (ref "LED3") (pin "3") (pinfunction "BLUE_A_3") (pintype "bidirectional"))
    )
    (net (code "79") (name "RGB_G") (class "Default")
      (node (ref "IC2") (pin "1") (pinfunction "QB_1") (pintype "tri_state"))
      (node (ref "LED3") (pin "1") (pinfunction "GREEN_A_1") (pintype "bidirectional"))
    )
    (net (code "80") (name "RGB_R") (class "Default")
      (node (ref "IC2") (pin "15") (pinfunction "QA_15") (pintype "tri_state"))
      (node (ref "LED3") (pin "2") (pinfunction "RED_A_2") (pintype "bidirectional"))
    )
    (net (code "81") (name "RST") (class "Default")
      (node (ref "C16") (pin "1") (pinfunction "1_1") (pintype "passive"))
      (node (ref "ISP") (pin "5") (pinfunction "RST_5") (pintype "output"))
      (node (ref "R4") (pin "1") (pinfunction "1_1") (pintype "passive"))
      (node (ref "S1") (pin "3") (pinfunction "3_3") (pintype "passive"))
      (node (ref "S1") (pin "4") (pinfunction "4_4") (pintype "passive"))
      (node (ref "U2") (pin "13") (pinfunction "/RESET_13") (pintype "bidirectional"))
    )
    (net (code "82") (name "RX") (class "Default")
      (node (ref "JP5") (pin "4") (pinfunction "4_4") (pintype "passive"))
      (node (ref "U2") (pin "20") (pinfunction "PD2(INT2/RXD1)_20") (pintype "bidirectional"))
    )
    (net (code "83") (name "SCK") (class "Default")
      (node (ref "IC1") (pin "11") (pinfunction "SCK_11") (pintype "input"))
      (node (ref "IC2") (pin "11") (pinfunction "SCK_11") (pintype "input"))
      (node (ref "ISP") (pin "3") (pinfunction "SCK_3") (pintype "output"))
      (node (ref "JP2") (pin "5") (pinfunction "5_5") (pintype "passive"))
      (node (ref "JP5") (pin "14") (pinfunction "14_14") (pintype "passive"))
      (node (ref "U2") (pin "9") (pinfunction "PB1(SCK)_9") (pintype "bidirectional"))
    )
    (net (code "84") (name "SENSE_GND") (class "Default")
      (node (ref "Q5") (pin "3") (pinfunction "D_3") (pintype "passive"))
      (node (ref "R21") (pin "2") (pinfunction "2_2") (pintype "passive"))
      (node (ref "R22") (pin "2") (pinfunction "2_2") (pintype "passive"))
      (node (ref "R25") (pin "2") (pinfunction "2_2") (pintype "passive"))
      (node (ref "R26") (pin "2") (pinfunction "2_2") (pintype "passive"))
      (node (ref "R27") (pin "2") (pinfunction "2_2") (pintype "passive"))
      (node (ref "U$12") (pin "P$7") (pinfunction "7_P$7") (pintype "passive"))
      (node (ref "U$18") (pin "2") (pinfunction "K_2") (pintype "bidirectional"))
      (node (ref "U$19") (pin "2") (pinfunction "K_2") (pintype "bidirectional"))
      (node (ref "U$20") (pin "2") (pinfunction "K_2") (pintype "bidirectional"))
      (node (ref "U$21") (pin "2") (pinfunction "K_2") (pintype "bidirectional"))
      (node (ref "U$22") (pin "P$1") (pinfunction "1_P$1") (pintype "passive"))
      (node (ref "U$9") (pin "2") (pinfunction "K_2") (pintype "bidirectional"))
    )
    (net (code "85") (name "STEP_1_1") (class "Default")
      (node (ref "IC1") (pin "3") (pinfunction "QD_3") (pintype "tri_state"))
      (node (ref "U$1") (pin "5") (pinfunction "B_5") (pintype "passive"))
    )
    (net (code "86") (name "STEP_1_2") (class "Default")
      (node (ref "IC1") (pin "2") (pinfunction "QC_2") (pintype "tri_state"))
      (node (ref "U$1") (pin "2") (pinfunction "B_2") (pintype "passive"))
    )
    (net (code "87") (name "STEP_1_3") (class "Default")
      (node (ref "IC1") (pin "1") (pinfunction "QB_1") (pintype "tri_state"))
      (node (ref "U$2") (pin "5") (pinfunction "B_5") (pintype "passive"))
    )
    (net (code "88") (name "STEP_1_4") (class "Default")
      (node (ref "IC1") (pin "15") (pinfunction "QA_15") (pintype "tri_state"))
      (node (ref "U$2") (pin "2") (pinfunction "B_2") (pintype "passive"))
    )
    (net (code "89") (name "STEP_2_1") (class "Default")
      (node (ref "IC1") (pin "7") (pinfunction "QH_7") (pintype "tri_state"))
      (node (ref "U$7") (pin "5") (pinfunction "B_5") (pintype "passive"))
    )
    (net (code "90") (name "STEP_2_2") (class "Default")
      (node (ref "IC1") (pin "6") (pinfunction "QG_6") (pintype "tri_state"))
      (node (ref "U$7") (pin "2") (pinfunction "B_2") (pintype "passive"))
    )
    (net (code "91") (name "STEP_2_3") (class "Default")
      (node (ref "IC1") (pin "5") (pinfunction "QF_5") (pintype "tri_state"))
      (node (ref "U$8") (pin "5") (pinfunction "B_5") (pintype "passive"))
    )
    (net (code "92") (name "STEP_2_4") (class "Default")
      (node (ref "IC1") (pin "4") (pinfunction "QE_4") (pintype "tri_state"))
      (node (ref "U$8") (pin "2") (pinfunction "B_2") (pintype "passive"))
    )
    (net (code "93") (name "STEP_3_1") (class "Default")
      (node (ref "IC2") (pin "7") (pinfunction "QH_7") (pintype "tri_state"))
      (node (ref "U$15") (pin "5") (pinfunction "B_5") (pintype "passive"))
    )
    (net (code "94") (name "STEP_3_2") (class "Default")
      (node (ref "IC2") (pin "6") (pinfunction "QG_6") (pintype "tri_state"))
      (node (ref "U$15") (pin "2") (pinfunction "B_2") (pintype "passive"))
    )
    (net (code "95") (name "STEP_3_3") (class "Default")
      (node (ref "IC2") (pin "5") (pinfunction "QF_5") (pintype "tri_state"))
      (node (ref "U$16") (pin "5") (pinfunction "B_5") (pintype "passive"))
    )
    (net (code "96") (name "STEP_3_4") (class "Default")
      (node (ref "IC2") (pin "4") (pinfunction "QE_4") (pintype "tri_state"))
      (node (ref "U$16") (pin "2") (pinfunction "B_2") (pintype "passive"))
    )
    (net (code "97") (name "TX") (class "Default")
      (node (ref "JP5") (pin "2") (pinfunction "2_2") (pintype "passive"))
      (node (ref "U2") (pin "21") (pinfunction "PD3(INT3/TXD1)_21") (pintype "bidirectional"))
    )
    (net (code "98") (name "VCC") (class "Default")
      (node (ref "D1") (pin "P$1") (pinfunction "C_P$1") (pintype "passive"))
      (node (ref "D2") (pin "P$1") (pinfunction "C_P$1") (pintype "passive"))
      (node (ref "IC1") (pin "10") (pinfunction "SCL_10") (pintype "input"))
      (node (ref "IC2") (pin "10") (pinfunction "SCL_10") (pintype "input"))
      (node (ref "ISP") (pin "2") (pinfunction "VCC_2") (pintype "power_in"))
      (node (ref "JP3") (pin "1") (pinfunction "1_1") (pintype "passive"))
      (node (ref "JP5") (pin "7") (pinfunction "7_7") (pintype "passive"))
      (node (ref "JP5") (pin "8") (pinfunction "8_8") (pintype "passive"))
      (node (ref "Q3") (pin "1") (pinfunction "G_1") (pintype "passive"))
      (node (ref "R15") (pin "1") (pinfunction "1_1") (pintype "passive"))
      (node (ref "R16") (pin "1") (pinfunction "1_1") (pintype "passive"))
      (node (ref "R17") (pin "1") (pinfunction "1_1") (pintype "passive"))
      (node (ref "R20") (pin "1") (pinfunction "1_1") (pintype "passive"))
      (node (ref "R28") (pin "1") (pinfunction "1_1") (pintype "passive"))
      (node (ref "R29") (pin "1") (pinfunction "1_1") (pintype "passive"))
      (node (ref "R4") (pin "2") (pinfunction "2_2") (pintype "passive"))
      (node (ref "R5") (pin "1") (pinfunction "1_1") (pintype "passive"))
      (node (ref "U$11") (pin "1") (pinfunction "IN_1") (pintype "input"))
      (node (ref "U$11") (pin "3") (pinfunction "EN_3") (pintype "input"))
      (node (ref "U$12") (pin "P$1") (pinfunction "1_P$1") (pintype "passive"))
      (node (ref "U$13") (pin "1") (pinfunction "C_1") (pintype "passive"))
      (node (ref "U$14") (pin "2") (pinfunction "VCC_2") (pintype "power_in"))
      (node (ref "U$18") (pin "3") (pinfunction "C_3") (pintype "bidirectional"))
      (node (ref "U$19") (pin "3") (pinfunction "C_3") (pintype "bidirectional"))
      (node (ref "U$20") (pin "3") (pinfunction "C_3") (pintype "bidirectional"))
      (node (ref "U$21") (pin "3") (pinfunction "C_3") (pintype "bidirectional"))
      (node (ref "U$22") (pin "P$7") (pinfunction "7_P$7") (pintype "passive"))
      (node (ref "U$3") (pin "1") (pinfunction "C_1") (pintype "passive"))
      (node (ref "U$4") (pin "1") (pinfunction "C_1") (pintype "passive"))
      (node (ref "U$6") (pin "16") (pinfunction "VDD_16") (pintype "bidirectional"))
      (node (ref "U$9") (pin "3") (pinfunction "C_3") (pintype "bidirectional"))
      (node (ref "U2") (pin "14") (pinfunction "VCC_14") (pintype "bidirectional"))
      (node (ref "U2") (pin "2") (pinfunction "UVCC_2") (pintype "bidirectional"))
      (node (ref "U2") (pin "24") (pinfunction "AVCC_24") (pintype "bidirectional"))
      (node (ref "U2") (pin "34") (pinfunction "VCC1_34") (pintype "bidirectional"))
      (node (ref "U2") (pin "44") (pinfunction "AVCC1_44") (pintype "bidirectional"))
    )
    (net (code "99") (name "VCC_3V3") (class "Default")
      (node (ref "C11") (pin "1") (pinfunction "1_1") (pintype "passive"))
      (node (ref "C14") (pin "1") (pinfunction "1_1") (pintype "passive"))
      (node (ref "C15") (pin "1") (pinfunction "1_1") (pintype "passive"))
      (node (ref "C2") (pin "1") (pinfunction "1_1") (pintype "passive"))
      (node (ref "C9") (pin "1") (pinfunction "1_1") (pintype "passive"))
      (node (ref "JP2") (pin "3") (pinfunction "3_3") (pintype "passive"))
      (node (ref "JP5") (pin "9") (pinfunction "9_9") (pintype "passive"))
      (node (ref "R23") (pin "1") (pinfunction "1_1") (pintype "passive"))
      (node (ref "R24") (pin "1") (pinfunction "1_1") (pintype "passive"))
      (node (ref "R8") (pin "2") (pinfunction "2_2") (pintype "passive"))
      (node (ref "R9") (pin "2") (pinfunction "2_2") (pintype "passive"))
      (node (ref "U$10") (pin "1") (pinfunction "VDDIO_1") (pintype "bidirectional"))
      (node (ref "U$10") (pin "11") (pinfunction "INT1_11") (pintype "bidirectional"))
      (node (ref "U$10") (pin "14") (pinfunction "VDD_14") (pintype "bidirectional"))
      (node (ref "U$10") (pin "7") (pinfunction "SA0_7") (pintype "bidirectional"))
      (node (ref "U$10") (pin "9") (pinfunction "INT2_9") (pintype "bidirectional"))
      (node (ref "U$11") (pin "5") (pinfunction "OUT_5") (pintype "passive"))
      (node (ref "U1") (pin "13") (pinfunction "VDDIO_13") (pintype "bidirectional"))
      (node (ref "U1") (pin "2") (pinfunction "VDD_2") (pintype "bidirectional"))
      (node (ref "U1") (pin "4") (pinfunction "S1_4") (pintype "bidirectional"))
    )
    (net (code "100") (name "V_BATT") (class "Default")
      (node (ref "JP1") (pin "2") (pinfunction "1_2") (pintype "passive"))
      (node (ref "Q7") (pin "2") (pinfunction "S_2") (pintype "passive"))
      (node (ref "R3") (pin "1") (pinfunction "1_1") (pintype "passive"))
      (node (ref "R7") (pin "2") (pinfunction "2_2") (pintype "passive"))
    )
    (net (code "101") (name "V_USB") (class "Default")
      (node (ref "D1") (pin "P$2") (pinfunction "A_P$2") (pintype "passive"))
      (node (ref "F1") (pin "2") (pinfunction "2_2") (pintype "bidirectional"))
    )
    (net (code "102") (name "ZK_CS") (class "Default")
      (node (ref "JP2") (pin "2") (pinfunction "2_2") (pintype "passive"))
    )
    (net (code "103") (name "ZK_SO") (class "Default")
      (node (ref "JP2") (pin "1") (pinfunction "1_1") (pintype "passive"))
    )
    (net (code "104") (name "unconnected-(IC2A-QH*-Pad9)") (class "Default")
      (node (ref "IC2") (pin "9") (pinfunction "QH*_9") (pintype "tri_state"))
    )
    (net (code "105") (name "unconnected-(U$11-BP-Pad4)") (class "Default")
      (node (ref "U$11") (pin "4") (pinfunction "BP_4") (pintype "input"))
    )
    (net (code "106") (name "unconnected-(U1-DRDY-Pad15)") (class "Default")
      (node (ref "U1") (pin "15") (pinfunction "DRDY_15") (pintype "bidirectional"))
    )
    (net (code "107") (name "unconnected-(U1-NC-Pad3)") (class "Default")
      (node (ref "U1") (pin "3") (pinfunction "NC_3") (pintype "bidirectional"))
    )
    (net (code "108") (name "unconnected-(U1-NC-Pad5)") (class "Default")
      (node (ref "U1") (pin "5") (pinfunction "NC_5") (pintype "bidirectional"))
    )
    (net (code "109") (name "unconnected-(U1-NC-Pad6)") (class "Default")
      (node (ref "U1") (pin "6") (pinfunction "NC_6") (pintype "bidirectional"))
    )
    (net (code "110") (name "unconnected-(U1-NC-Pad7)") (class "Default")
      (node (ref "U1") (pin "7") (pinfunction "NC_7") (pintype "bidirectional"))
    )
    (net (code "111") (name "unconnected-(U1-NC-Pad14)") (class "Default")
      (node (ref "U1") (pin "14") (pinfunction "NC_14") (pintype "bidirectional"))
    )
  )
)
